# display_Rev-B.net
KiCad netlist of a schematic drawn in EAGLE
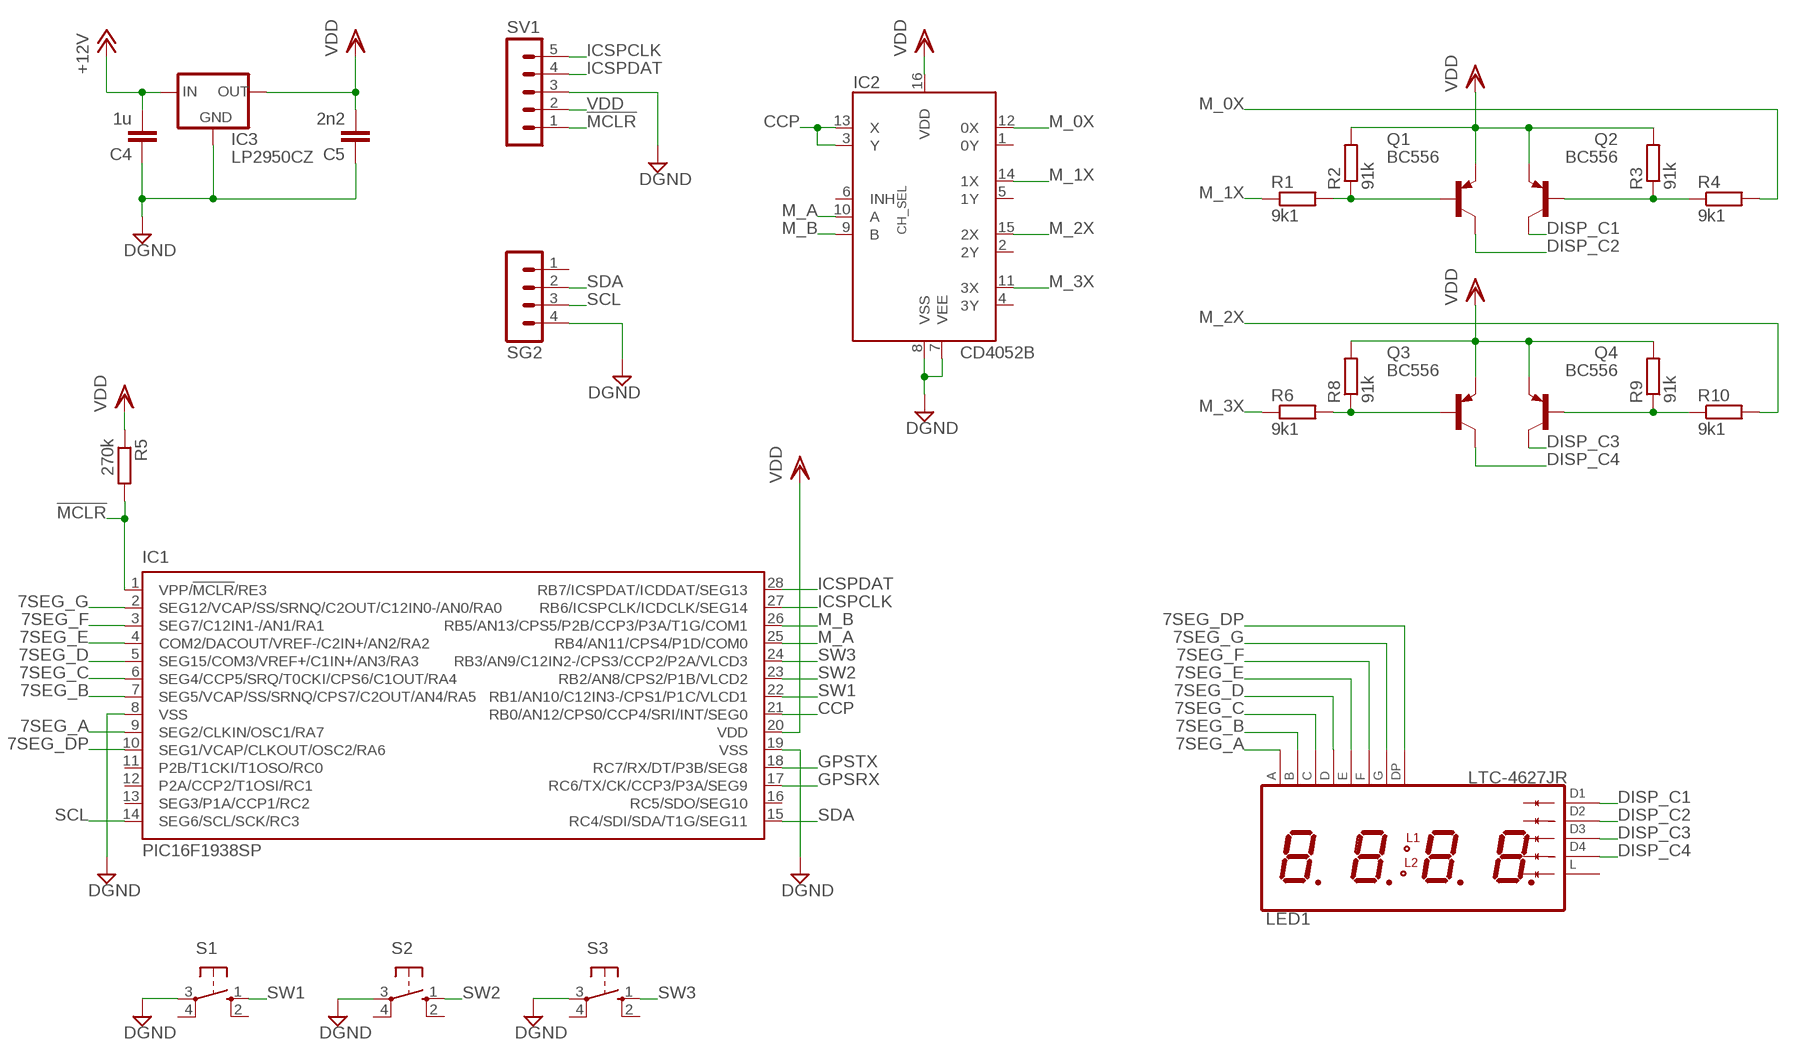
[diagram p0: schematic, sheet 1]

(export (version "E")
  (design (tool "Eeschema 10.0.6"))
  (components
    (comp (ref "C4")
      (value "1u")
      (footprint "eagle-import:C5B2.5")
      (libsource (lib "eagle-import") (part "C5/2.5"))
    )
    (comp (ref "C5")
      (value "2n2")
      (footprint "eagle-import:C5B2.5")
      (libsource (lib "eagle-import") (part "C5/2.5"))
    )
    (comp (ref "IC1")
      (value "PIC16F1938SP")
      (footprint "eagle-import:DIL28-3")
      (fields (field (name "MPN") "PIC16F1938-I/SP"))
      (libsource (lib "eagle-import") (part "PIC16F19SP38"))
    )
    (comp (ref "IC2")
      (value "CD4052B")
      (footprint "eagle-import:DIL16")
      (libsource (lib "eagle-import") (part "CD4052B"))
    )
    (comp (ref "IC3")
      (value "LP2950CZ")
      (footprint "eagle-import:TO92")
      (libsource (lib "eagle-import") (part "LP2950?CZ-5.0"))
    )
    (comp (ref "LED1")
      (value "LTC-4627JR")
      (footprint "eagle-import:7-SEG-LED-QUAD")
      (libsource (lib "eagle-import") (part "LTC-4627JR"))
    )
    (comp (ref "Q1")
      (value "BC556")
      (footprint "eagle-import:TO92-EBC")
      (libsource (lib "eagle-import") (part "BC556"))
    )
    (comp (ref "Q2")
      (value "BC556")
      (footprint "eagle-import:TO92-EBC")
      (libsource (lib "eagle-import") (part "BC556"))
    )
    (comp (ref "Q3")
      (value "BC556")
      (footprint "eagle-import:TO92-EBC")
      (libsource (lib "eagle-import") (part "BC556"))
    )
    (comp (ref "Q4")
      (value "BC556")
      (footprint "eagle-import:TO92-EBC")
      (libsource (lib "eagle-import") (part "BC556"))
    )
    (comp (ref "R1")
      (value "9k1")
      (footprint "eagle-import:0204_5")
      (libsource (lib "eagle-import") (part "R-EU_0204/5"))
    )
    (comp (ref "R2")
      (value "91k")
      (footprint "eagle-import:0204_5")
      (libsource (lib "eagle-import") (part "R-EU_0204/5"))
    )
    (comp (ref "R3")
      (value "91k")
      (footprint "eagle-import:0204_5")
      (libsource (lib "eagle-import") (part "R-EU_0204/5"))
    )
    (comp (ref "R4")
      (value "9k1")
      (footprint "eagle-import:0204_5")
      (libsource (lib "eagle-import") (part "R-EU_0204/5"))
    )
    (comp (ref "R5")
      (value "270k")
      (footprint "eagle-import:M1206")
      (libsource (lib "eagle-import") (part "R-EU_M1206"))
    )
    (comp (ref "R6")
      (value "9k1")
      (footprint "eagle-import:0204_5")
      (libsource (lib "eagle-import") (part "R-EU_0204/5"))
    )
    (comp (ref "R8")
      (value "91k")
      (footprint "eagle-import:0204_5")
      (libsource (lib "eagle-import") (part "R-EU_0204/5"))
    )
    (comp (ref "R9")
      (value "91k")
      (footprint "eagle-import:0204_5")
      (libsource (lib "eagle-import") (part "R-EU_0204/5"))
    )
    (comp (ref "R10")
      (value "9k1")
      (footprint "eagle-import:0204_5")
      (libsource (lib "eagle-import") (part "R-EU_0204/5"))
    )
    (comp (ref "S1")
      (value "10-XX")
      (footprint "eagle-import:B3F-10XX")
      (fields (field (name "MPN") "B3F-1000"))
      (libsource (lib "eagle-import") (part "10-XX"))
    )
    (comp (ref "S2")
      (value "10-XX")
      (footprint "eagle-import:B3F-10XX")
      (fields (field (name "MPN") "B3F-1000"))
      (libsource (lib "eagle-import") (part "10-XX"))
    )
    (comp (ref "S3")
      (value "10-XX")
      (footprint "eagle-import:B3F-10XX")
      (fields (field (name "MPN") "B3F-1000"))
      (libsource (lib "eagle-import") (part "10-XX"))
    )
    (comp (ref "SG2")
      (value "MA04-1")
      (footprint "eagle-import:MA04-1")
      (libsource (lib "eagle-import") (part "MA04-1"))
    )
    (comp (ref "SV1")
      (value "MA05-1")
      (footprint "eagle-import:MA05-1")
      (libsource (lib "eagle-import") (part "MA05-1"))
    )
  )
  (nets
    (net (code "1") (name "+12V") (class "Default")
      (node (ref "C4") (pin "2") (pinfunction "2_2") (pintype "passive"))
      (node (ref "IC3") (pin "3") (pinfunction "IN_3") (pintype "input"))
    )
    (net (code "2") (name "/7SEG_A") (class "Default")
      (node (ref "IC1") (pin "9") (pinfunction "SEG2/CLKIN/OSC1/RA7_9") (pintype "bidirectional"))
      (node (ref "LED1") (pin "P$14") (pinfunction "A_P$14") (pintype "bidirectional"))
    )
    (net (code "3") (name "/7SEG_B") (class "Default")
      (node (ref "IC1") (pin "7") (pinfunction "SEG5/VCAP/SS/SRNQ/CPS7/C2OUT/AN4/RA5_7") (pintype "bidirectional"))
      (node (ref "LED1") (pin "P$16") (pinfunction "B_P$16") (pintype "bidirectional"))
    )
    (net (code "4") (name "/7SEG_C") (class "Default")
      (node (ref "IC1") (pin "6") (pinfunction "SEG4/CCP5/SRQ/T0CKI/CPS6/C1OUT/RA4_6") (pintype "bidirectional"))
      (node (ref "LED1") (pin "P$13") (pinfunction "C_P$13") (pintype "bidirectional"))
    )
    (net (code "5") (name "/7SEG_D") (class "Default")
      (node (ref "IC1") (pin "5") (pinfunction "SEG15/COM3/VREF+/C1IN+/AN3/RA3_5") (pintype "bidirectional"))
      (node (ref "LED1") (pin "P$3") (pinfunction "D_P$3") (pintype "bidirectional"))
    )
    (net (code "6") (name "/7SEG_DP") (class "Default")
      (node (ref "IC1") (pin "10") (pinfunction "SEG1/VCAP/CLKOUT/OSC2/RA6_10") (pintype "bidirectional"))
      (node (ref "LED1") (pin "P$7") (pinfunction "DP_P$7") (pintype "bidirectional"))
    )
    (net (code "7") (name "/7SEG_E") (class "Default")
      (node (ref "IC1") (pin "4") (pinfunction "COM2/DACOUT/VREF-/C2IN+/AN2/RA2_4") (pintype "bidirectional"))
      (node (ref "LED1") (pin "P$5") (pinfunction "E_P$5") (pintype "bidirectional"))
    )
    (net (code "8") (name "/7SEG_F") (class "Default")
      (node (ref "IC1") (pin "3") (pinfunction "SEG7/C12IN1-/AN1/RA1_3") (pintype "bidirectional"))
      (node (ref "LED1") (pin "P$11") (pinfunction "F_P$11") (pintype "bidirectional"))
    )
    (net (code "9") (name "/7SEG_G") (class "Default")
      (node (ref "IC1") (pin "2") (pinfunction "SEG12/VCAP/SS/SRNQ/C2OUT/C12IN0-/AN0/RA0_2") (pintype "bidirectional"))
      (node (ref "LED1") (pin "P$15") (pinfunction "G_P$15") (pintype "bidirectional"))
    )
    (net (code "10") (name "/CCP") (class "Default")
      (node (ref "IC1") (pin "21") (pinfunction "RB0/AN12/CPS0/CCP4/SRI/INT/SEG0_21") (pintype "bidirectional"))
      (node (ref "IC2") (pin "13") (pinfunction "X_13") (pintype "bidirectional"))
      (node (ref "IC2") (pin "3") (pinfunction "Y_3") (pintype "bidirectional"))
    )
    (net (code "11") (name "/DISP_C1") (class "Default")
      (node (ref "LED1") (pin "P$1") (pinfunction "D1_P$1") (pintype "bidirectional"))
      (node (ref "Q2") (pin "C") (pinfunction "C_C") (pintype "passive"))
    )
    (net (code "12") (name "/DISP_C2") (class "Default")
      (node (ref "LED1") (pin "P$2") (pinfunction "D2_P$2") (pintype "bidirectional"))
      (node (ref "Q1") (pin "C") (pinfunction "C_C") (pintype "passive"))
    )
    (net (code "13") (name "/DISP_C3") (class "Default")
      (node (ref "LED1") (pin "P$6") (pinfunction "D3_P$6") (pintype "bidirectional"))
      (node (ref "Q4") (pin "C") (pinfunction "C_C") (pintype "passive"))
    )
    (net (code "14") (name "/DISP_C4") (class "Default")
      (node (ref "LED1") (pin "P$8") (pinfunction "D4_P$8") (pintype "bidirectional"))
      (node (ref "Q3") (pin "C") (pinfunction "C_C") (pintype "passive"))
    )
    (net (code "15") (name "/GPSRX") (class "Default")
      (node (ref "IC1") (pin "17") (pinfunction "RC6/TX/CK/CCP3/P3A/SEG9_17") (pintype "bidirectional"))
    )
    (net (code "16") (name "/GPSTX") (class "Default")
      (node (ref "IC1") (pin "18") (pinfunction "RC7/RX/DT/P3B/SEG8_18") (pintype "bidirectional"))
    )
    (net (code "17") (name "/ICSPCLK") (class "Default")
      (node (ref "IC1") (pin "27") (pinfunction "RB6/ICSPCLK/ICDCLK/SEG14_27") (pintype "bidirectional"))
      (node (ref "SV1") (pin "5") (pinfunction "5_5") (pintype "passive"))
    )
    (net (code "18") (name "/ICSPDAT") (class "Default")
      (node (ref "IC1") (pin "28") (pinfunction "RB7/ICSPDAT/ICDDAT/SEG13_28") (pintype "bidirectional"))
      (node (ref "SV1") (pin "4") (pinfunction "4_4") (pintype "passive"))
    )
    (net (code "19") (name "/M_0X") (class "Default")
      (node (ref "IC2") (pin "12") (pinfunction "0X_12") (pintype "bidirectional"))
      (node (ref "R4") (pin "2") (pinfunction "2_2") (pintype "passive"))
    )
    (net (code "20") (name "/M_1X") (class "Default")
      (node (ref "IC2") (pin "14") (pinfunction "1X_14") (pintype "bidirectional"))
      (node (ref "R1") (pin "1") (pinfunction "1_1") (pintype "passive"))
    )
    (net (code "21") (name "/M_2X") (class "Default")
      (node (ref "IC2") (pin "15") (pinfunction "2X_15") (pintype "bidirectional"))
      (node (ref "R10") (pin "2") (pinfunction "2_2") (pintype "passive"))
    )
    (net (code "22") (name "/M_3X") (class "Default")
      (node (ref "IC2") (pin "11") (pinfunction "3X_11") (pintype "bidirectional"))
      (node (ref "R6") (pin "1") (pinfunction "1_1") (pintype "passive"))
    )
    (net (code "23") (name "/M_A") (class "Default")
      (node (ref "IC1") (pin "25") (pinfunction "RB4/AN11/CPS4/P1D/COM0_25") (pintype "bidirectional"))
      (node (ref "IC2") (pin "10") (pinfunction "A_10") (pintype "bidirectional"))
    )
    (net (code "24") (name "/M_B") (class "Default")
      (node (ref "IC1") (pin "26") (pinfunction "RB5/AN13/CPS5/P2B/CCP3/P3A/T1G/COM1_26") (pintype "bidirectional"))
      (node (ref "IC2") (pin "9") (pinfunction "B_9") (pintype "bidirectional"))
    )
    (net (code "25") (name "/SCL") (class "Default")
      (node (ref "IC1") (pin "14") (pinfunction "SEG6/SCL/SCK/RC3_14") (pintype "bidirectional"))
      (node (ref "SG2") (pin "3") (pinfunction "3_3") (pintype "passive"))
    )
    (net (code "26") (name "/SDA") (class "Default")
      (node (ref "IC1") (pin "15") (pinfunction "RC4/SDI/SDA/T1G/SEG11_15") (pintype "bidirectional"))
      (node (ref "SG2") (pin "2") (pinfunction "2_2") (pintype "passive"))
    )
    (net (code "27") (name "/SW1") (class "Default")
      (node (ref "IC1") (pin "22") (pinfunction "RB1/AN10/C12IN3-/CPS1/P1C/VLCD1_22") (pintype "bidirectional"))
      (node (ref "S1") (pin "1") (pinfunction "S_1") (pintype "passive"))
    )
    (net (code "28") (name "/SW2") (class "Default")
      (node (ref "IC1") (pin "23") (pinfunction "RB2/AN8/CPS2/P1B/VLCD2_23") (pintype "bidirectional"))
      (node (ref "S2") (pin "1") (pinfunction "S_1") (pintype "passive"))
    )
    (net (code "29") (name "/SW3") (class "Default")
      (node (ref "IC1") (pin "24") (pinfunction "RB3/AN9/C12IN2-/CPS3/CCP2/P2A/VLCD3_24") (pintype "bidirectional"))
      (node (ref "S3") (pin "1") (pinfunction "S_1") (pintype "passive"))
    )
    (net (code "30") (name "/~{MCLR}") (class "Default")
      (node (ref "IC1") (pin "1") (pinfunction "VPP/~{MCLR}/RE3_1") (pintype "input"))
      (node (ref "R5") (pin "2") (pinfunction "2_2") (pintype "passive"))
      (node (ref "SV1") (pin "1") (pinfunction "1_1") (pintype "passive"))
    )
    (net (code "31") (name "DGND") (class "Default")
      (node (ref "C4") (pin "1") (pinfunction "1_1") (pintype "passive"))
      (node (ref "C5") (pin "1") (pinfunction "1_1") (pintype "passive"))
      (node (ref "IC1") (pin "19") (pinfunction "VSS_19") (pintype "power_in"))
      (node (ref "IC1") (pin "8") (pinfunction "VSS_8") (pintype "power_in"))
      (node (ref "IC2") (pin "7") (pinfunction "VEE_7") (pintype "bidirectional"))
      (node (ref "IC2") (pin "8") (pinfunction "VSS_8") (pintype "bidirectional"))
      (node (ref "IC3") (pin "2") (pinfunction "GND_2") (pintype "input"))
      (node (ref "S1") (pin "3") (pinfunction "P_3") (pintype "passive"))
      (node (ref "S2") (pin "3") (pinfunction "P_3") (pintype "passive"))
      (node (ref "S3") (pin "3") (pinfunction "P_3") (pintype "passive"))
      (node (ref "SG2") (pin "4") (pinfunction "4_4") (pintype "passive"))
      (node (ref "SV1") (pin "3") (pinfunction "3_3") (pintype "passive"))
    )
    (net (code "32") (name "Net-(Q1-PadB)") (class "Default")
      (node (ref "Q1") (pin "B") (pinfunction "B_B") (pintype "passive"))
      (node (ref "R1") (pin "2") (pinfunction "2_2") (pintype "passive"))
      (node (ref "R2") (pin "1") (pinfunction "1_1") (pintype "passive"))
    )
    (net (code "33") (name "Net-(Q2-PadB)") (class "Default")
      (node (ref "Q2") (pin "B") (pinfunction "B_B") (pintype "passive"))
      (node (ref "R3") (pin "1") (pinfunction "1_1") (pintype "passive"))
      (node (ref "R4") (pin "1") (pinfunction "1_1") (pintype "passive"))
    )
    (net (code "34") (name "Net-(Q3-PadB)") (class "Default")
      (node (ref "Q3") (pin "B") (pinfunction "B_B") (pintype "passive"))
      (node (ref "R6") (pin "2") (pinfunction "2_2") (pintype "passive"))
      (node (ref "R8") (pin "1") (pinfunction "1_1") (pintype "passive"))
    )
    (net (code "35") (name "Net-(Q4-PadB)") (class "Default")
      (node (ref "Q4") (pin "B") (pinfunction "B_B") (pintype "passive"))
      (node (ref "R10") (pin "1") (pinfunction "1_1") (pintype "passive"))
      (node (ref "R9") (pin "1") (pinfunction "1_1") (pintype "passive"))
    )
    (net (code "36") (name "VDD") (class "Default")
      (node (ref "C5") (pin "2") (pinfunction "2_2") (pintype "passive"))
      (node (ref "IC1") (pin "20") (pinfunction "VDD_20") (pintype "power_in"))
      (node (ref "IC2") (pin "16") (pinfunction "VDD_16") (pintype "bidirectional"))
      (node (ref "IC3") (pin "1") (pinfunction "OUT_1") (pintype "passive"))
      (node (ref "Q1") (pin "E") (pinfunction "E_E") (pintype "passive"))
      (node (ref "Q2") (pin "E") (pinfunction "E_E") (pintype "passive"))
      (node (ref "Q3") (pin "E") (pinfunction "E_E") (pintype "passive"))
      (node (ref "Q4") (pin "E") (pinfunction "E_E") (pintype "passive"))
      (node (ref "R2") (pin "2") (pinfunction "2_2") (pintype "passive"))
      (node (ref "R3") (pin "2") (pinfunction "2_2") (pintype "passive"))
      (node (ref "R5") (pin "1") (pinfunction "1_1") (pintype "passive"))
      (node (ref "R8") (pin "2") (pinfunction "2_2") (pintype "passive"))
      (node (ref "R9") (pin "2") (pinfunction "2_2") (pintype "passive"))
      (node (ref "SV1") (pin "2") (pinfunction "2_2") (pintype "passive"))
    )
    (net (code "37") (name "unconnected-(IC1-P2A{slash}CCP2{slash}T1OSI{slash}RC1-Pad12)") (class "Default")
      (node (ref "IC1") (pin "12") (pinfunction "P2A/CCP2/T1OSI/RC1_12") (pintype "bidirectional"))
    )
    (net (code "38") (name "unconnected-(IC1-P2B{slash}T1CKI{slash}T1OSO{slash}RC0-Pad11)") (class "Default")
      (node (ref "IC1") (pin "11") (pinfunction "P2B/T1CKI/T1OSO/RC0_11") (pintype "bidirectional"))
    )
    (net (code "39") (name "unconnected-(IC1-RC5{slash}SDO{slash}SEG10-Pad16)") (class "Default")
      (node (ref "IC1") (pin "16") (pinfunction "RC5/SDO/SEG10_16") (pintype "bidirectional"))
    )
    (net (code "40") (name "unconnected-(IC1-SEG3{slash}P1A{slash}CCP1{slash}RC2-Pad13)") (class "Default")
      (node (ref "IC1") (pin "13") (pinfunction "SEG3/P1A/CCP1/RC2_13") (pintype "bidirectional"))
    )
    (net (code "41") (name "unconnected-(IC2-0Y-Pad1)") (class "Default")
      (node (ref "IC2") (pin "1") (pinfunction "0Y_1") (pintype "bidirectional"))
    )
    (net (code "42") (name "unconnected-(IC2-1Y-Pad5)") (class "Default")
      (node (ref "IC2") (pin "5") (pinfunction "1Y_5") (pintype "bidirectional"))
    )
    (net (code "43") (name "unconnected-(IC2-2Y-Pad2)") (class "Default")
      (node (ref "IC2") (pin "2") (pinfunction "2Y_2") (pintype "bidirectional"))
    )
    (net (code "44") (name "unconnected-(IC2-3Y-Pad4)") (class "Default")
      (node (ref "IC2") (pin "4") (pinfunction "3Y_4") (pintype "bidirectional"))
    )
    (net (code "45") (name "unconnected-(IC2-INH-Pad6)") (class "Default")
      (node (ref "IC2") (pin "6") (pinfunction "INH_6") (pintype "bidirectional"))
    )
    (net (code "46") (name "unconnected-(LED1-L-PadP$4)") (class "Default")
      (node (ref "LED1") (pin "P$4") (pinfunction "L_P$4") (pintype "bidirectional"))
    )
    (net (code "47") (name "unconnected-(S1-P1-Pad4)") (class "Default")
      (node (ref "S1") (pin "4") (pinfunction "P1_4") (pintype "passive"))
    )
    (net (code "48") (name "unconnected-(S1-S1-Pad2)") (class "Default")
      (node (ref "S1") (pin "2") (pinfunction "S1_2") (pintype "passive"))
    )
    (net (code "49") (name "unconnected-(S2-P1-Pad4)") (class "Default")
      (node (ref "S2") (pin "4") (pinfunction "P1_4") (pintype "passive"))
    )
    (net (code "50") (name "unconnected-(S2-S1-Pad2)") (class "Default")
      (node (ref "S2") (pin "2") (pinfunction "S1_2") (pintype "passive"))
    )
    (net (code "51") (name "unconnected-(S3-P1-Pad4)") (class "Default")
      (node (ref "S3") (pin "4") (pinfunction "P1_4") (pintype "passive"))
    )
    (net (code "52") (name "unconnected-(S3-S1-Pad2)") (class "Default")
      (node (ref "S3") (pin "2") (pinfunction "S1_2") (pintype "passive"))
    )
    (net (code "53") (name "unconnected-(SG2-Pad1)") (class "Default")
      (node (ref "SG2") (pin "1") (pinfunction "1_1") (pintype "passive"))
    )
  )
)
